# Demo.net
KiCad netlist of a schematic drawn in Altium Designer
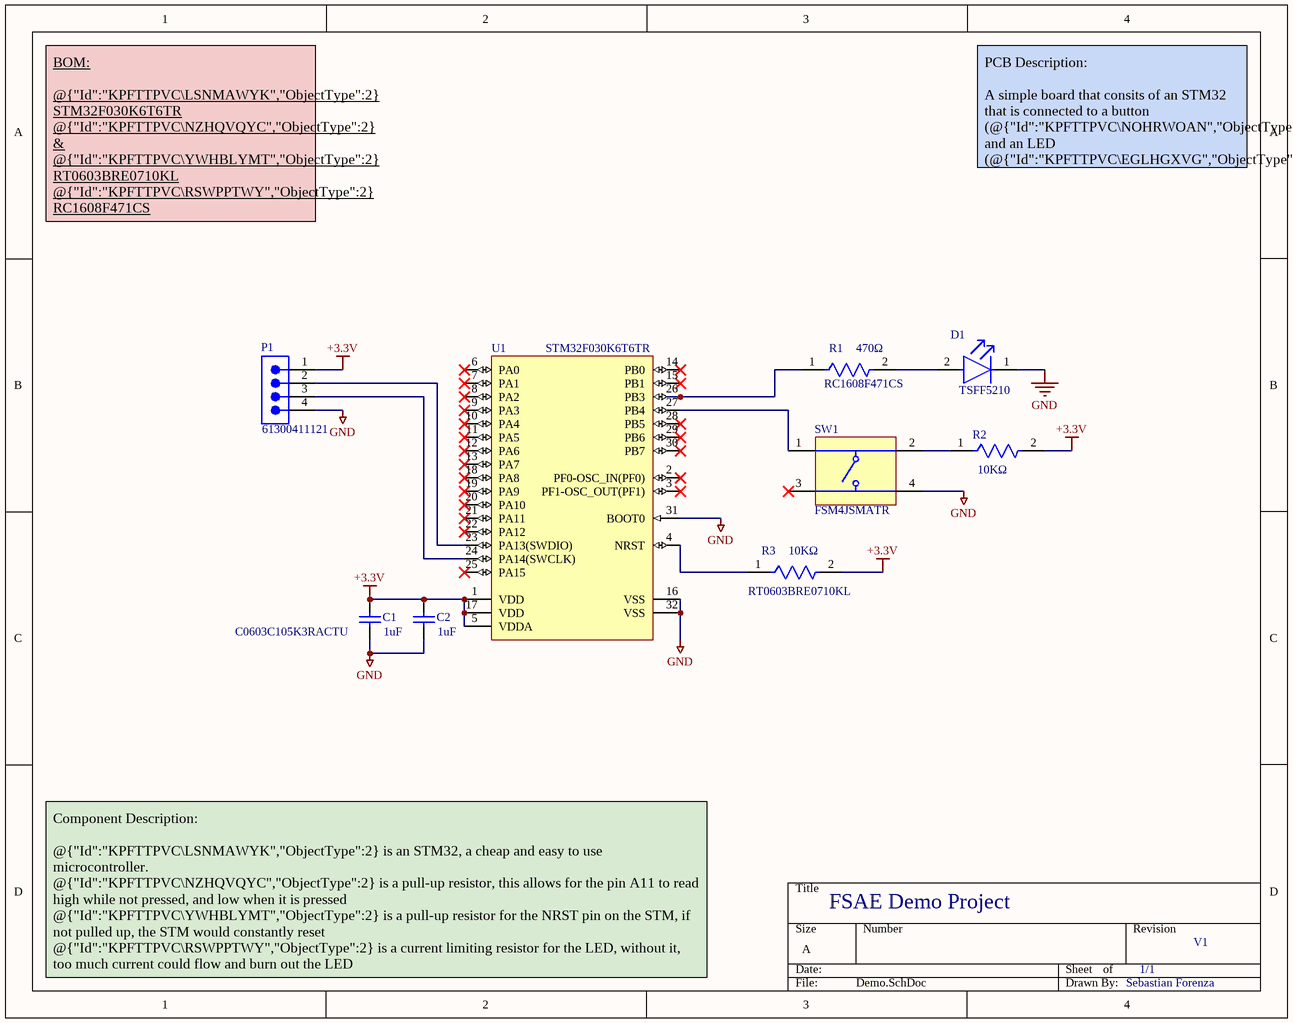
[diagram p0: Demo.SchDoc]

(export (version "E")
  (design (tool "Eeschema 10.0.6"))
  (components
    (comp (ref "C1")
      (value "C0603C105K3RACTU")
      (footprint "CAPC1608X87X35ML15T15")
      (fields (field (name "MANUFACTURER") "Kemet") (field (name "CAPACITANCE") "1uF"))
      (libsource (lib "Altium Content Vault") (part "CAP"))
    )
    (comp (ref "C2")
      (value "C0603C105K3RACTU")
      (footprint "CAPC1608X87X35ML15T15")
      (fields (field (name "MANUFACTURER") "Kemet") (field (name "CAPACITANCE") "1uF"))
      (libsource (lib "Altium Content Vault") (part "CAP"))
    )
    (comp (ref "D1")
      (value "TSFF5210")
      (footprint "FP-6_544-5258_09-4-MFG")
      (description "TSFF5210 TSFF5210 IR LED, 870nm, T-1 3/4 (5mm) Through Hole package")
      (libsource (lib "Altium Content Vault") (part "8706943c75ba83719d021d2fdc84c58"))
    )
    (comp (ref "P1")
      (value "61300411121")
      (footprint "61300411121")
      (libsource (lib "Altium Content Vault") (part "Header_Male_1R_04P"))
    )
    (comp (ref "R1")
      (value "RC1608F471CS")
      (footprint "FP-RC1608-IPC_A")
      (description "Res Thick Film 0603 470Ω 1% 0.1W ±100ppm/°C Molded SMD T/R")
      (fields (field (name "TOLERANCE") "1%") (field (name "RESISTANCE") "470Ω"))
      (libsource (lib "Altium Content Vault") (part "1029c3af85768c4190bb7ad29bc67b5"))
    )
    (comp (ref "R2")
      (value "RT0603BRE0710KL")
      (footprint "FP-RT0603-IPC_A")
      (description "RES SMD 10K OHM 0.1% 1/10W 0603")
      (fields
        (field (name "TOLERANCE") "0.001")
        (field (name "OCTOPART") "https://octopart.com/rt0603bre0710kl-yageo-1273959")
        (field (name "RESISTANCE") "10KΩ")
      )
      (libsource (lib "Altium Content Vault") (part "1029c3af85768c4190bb7ad29bc67b5"))
    )
    (comp (ref "R3")
      (value "RT0603BRE0710KL")
      (footprint "FP-RT0603-IPC_A")
      (description "RES SMD 10K OHM 0.1% 1/10W 0603")
      (fields
        (field (name "TOLERANCE") "0.001")
        (field (name "OCTOPART") "https://octopart.com/rt0603bre0710kl-yageo-1273959")
        (field (name "RESISTANCE") "10KΩ")
      )
      (libsource (lib "Altium Content Vault") (part "1029c3af85768c4190bb7ad29bc67b5"))
    )
    (comp (ref "SW1")
      (value "FSM4JSMATR")
      (footprint "TECO-FSM4JSMATR_V")
      (description "Micro Miniature Push Button Switch FSM JSM, 50 mA, -35 to 85 degC, 4-Pin SMD, RoHS, Tape and Reel")
      (fields (field (name "MANUFACTURER") "TE Connectivity"))
      (libsource (lib "Altium Content Vault") (part "SW-SPST-4_A"))
    )
    (comp (ref "U1")
      (value "STM32F030K6T6TR")
      (footprint "STM-LQFP32_M")
      (fields (field (name "MANUFACTURER") "STMicroelectronics"))
      (libsource (lib "Altium Content Vault") (part "MC-ARM-STM32F030-LQFP32"))
    )
  )
  (nets
    (net (code "1") (name "+3.3V") (class "Default")
      (node (ref "C1") (pin "2") (pinfunction "2_2") (pintype "passive"))
      (node (ref "C2") (pin "2") (pinfunction "2_2") (pintype "passive"))
      (node (ref "P1") (pin "1") (pinfunction "1_1") (pintype "passive"))
      (node (ref "R2") (pin "2") (pinfunction "2_2") (pintype "passive"))
      (node (ref "R3") (pin "2") (pinfunction "2_2") (pintype "passive"))
      (node (ref "U1") (pin "1") (pinfunction "VDD_1") (pintype "power_in"))
      (node (ref "U1") (pin "17") (pinfunction "VDD_17") (pintype "power_in"))
      (node (ref "U1") (pin "5") (pinfunction "VDDA_5") (pintype "power_in"))
    )
    (net (code "2") (name "GND") (class "Default")
      (node (ref "C1") (pin "1") (pinfunction "1_1") (pintype "passive"))
      (node (ref "C2") (pin "1") (pinfunction "1_1") (pintype "passive"))
      (node (ref "D1") (pin "1") (pinfunction "C_1") (pintype "passive"))
      (node (ref "P1") (pin "4") (pinfunction "4_4") (pintype "passive"))
      (node (ref "SW1") (pin "4") (pinfunction "4_4") (pintype "passive"))
      (node (ref "U1") (pin "16") (pinfunction "VSS_16") (pintype "power_in"))
      (node (ref "U1") (pin "31") (pinfunction "BOOT0_31") (pintype "input"))
      (node (ref "U1") (pin "32") (pinfunction "VSS_32") (pintype "power_in"))
    )
    (net (code "3") (name "Net-(D1-A)") (class "Default")
      (node (ref "D1") (pin "2") (pinfunction "A_2") (pintype "passive"))
      (node (ref "R1") (pin "2") (pinfunction "2_2") (pintype "passive"))
    )
    (net (code "4") (name "Net-(R2-Pad1)") (class "Default")
      (node (ref "R2") (pin "1") (pinfunction "1_1") (pintype "passive"))
      (node (ref "SW1") (pin "2") (pinfunction "2_2") (pintype "passive"))
    )
    (net (code "5") (name "Net-(U1-NRST)") (class "Default")
      (node (ref "R3") (pin "1") (pinfunction "1_1") (pintype "passive"))
      (node (ref "U1") (pin "4") (pinfunction "NRST_4") (pintype "bidirectional"))
    )
    (net (code "6") (name "Net-(U1-PA13(SWDIO))") (class "Default")
      (node (ref "P1") (pin "2") (pinfunction "2_2") (pintype "passive"))
      (node (ref "U1") (pin "23") (pinfunction "PA13(SWDIO)_23") (pintype "bidirectional"))
    )
    (net (code "7") (name "Net-(U1-PA14(SWCLK))") (class "Default")
      (node (ref "P1") (pin "3") (pinfunction "3_3") (pintype "passive"))
      (node (ref "U1") (pin "24") (pinfunction "PA14(SWCLK)_24") (pintype "bidirectional"))
    )
    (net (code "8") (name "Net-(U1-PB3)") (class "Default")
      (node (ref "R1") (pin "1") (pinfunction "1_1") (pintype "passive"))
      (node (ref "U1") (pin "26") (pinfunction "PB3_26") (pintype "bidirectional"))
    )
    (net (code "9") (name "Net-(U1-PB4)") (class "Default")
      (node (ref "SW1") (pin "1") (pinfunction "1_1") (pintype "passive"))
      (node (ref "U1") (pin "27") (pinfunction "PB4_27") (pintype "bidirectional"))
    )
    (net (code "10") (name "unconnected-(SW1-Pad3)") (class "Default")
      (node (ref "SW1") (pin "3") (pinfunction "3_3") (pintype "passive+no_connect"))
    )
    (net (code "11") (name "unconnected-(U1-PA0-Pad6)") (class "Default")
      (node (ref "U1") (pin "6") (pinfunction "PA0_6") (pintype "bidirectional+no_connect"))
    )
    (net (code "12") (name "unconnected-(U1-PA1-Pad7)") (class "Default")
      (node (ref "U1") (pin "7") (pinfunction "PA1_7") (pintype "bidirectional+no_connect"))
    )
    (net (code "13") (name "unconnected-(U1-PA2-Pad8)") (class "Default")
      (node (ref "U1") (pin "8") (pinfunction "PA2_8") (pintype "bidirectional+no_connect"))
    )
    (net (code "14") (name "unconnected-(U1-PA3-Pad9)") (class "Default")
      (node (ref "U1") (pin "9") (pinfunction "PA3_9") (pintype "bidirectional+no_connect"))
    )
    (net (code "15") (name "unconnected-(U1-PA4-Pad10)") (class "Default")
      (node (ref "U1") (pin "10") (pinfunction "PA4_10") (pintype "bidirectional+no_connect"))
    )
    (net (code "16") (name "unconnected-(U1-PA5-Pad11)") (class "Default")
      (node (ref "U1") (pin "11") (pinfunction "PA5_11") (pintype "bidirectional+no_connect"))
    )
    (net (code "17") (name "unconnected-(U1-PA6-Pad12)") (class "Default")
      (node (ref "U1") (pin "12") (pinfunction "PA6_12") (pintype "bidirectional+no_connect"))
    )
    (net (code "18") (name "unconnected-(U1-PA7-Pad13)") (class "Default")
      (node (ref "U1") (pin "13") (pinfunction "PA7_13") (pintype "bidirectional+no_connect"))
    )
    (net (code "19") (name "unconnected-(U1-PA8-Pad18)") (class "Default")
      (node (ref "U1") (pin "18") (pinfunction "PA8_18") (pintype "bidirectional+no_connect"))
    )
    (net (code "20") (name "unconnected-(U1-PA9-Pad19)") (class "Default")
      (node (ref "U1") (pin "19") (pinfunction "PA9_19") (pintype "bidirectional+no_connect"))
    )
    (net (code "21") (name "unconnected-(U1-PA10-Pad20)") (class "Default")
      (node (ref "U1") (pin "20") (pinfunction "PA10_20") (pintype "bidirectional+no_connect"))
    )
    (net (code "22") (name "unconnected-(U1-PA11-Pad21)") (class "Default")
      (node (ref "U1") (pin "21") (pinfunction "PA11_21") (pintype "bidirectional+no_connect"))
    )
    (net (code "23") (name "unconnected-(U1-PA12-Pad22)") (class "Default")
      (node (ref "U1") (pin "22") (pinfunction "PA12_22") (pintype "bidirectional+no_connect"))
    )
    (net (code "24") (name "unconnected-(U1-PA15-Pad25)") (class "Default")
      (node (ref "U1") (pin "25") (pinfunction "PA15_25") (pintype "bidirectional+no_connect"))
    )
    (net (code "25") (name "unconnected-(U1-PB0-Pad14)") (class "Default")
      (node (ref "U1") (pin "14") (pinfunction "PB0_14") (pintype "bidirectional+no_connect"))
    )
    (net (code "26") (name "unconnected-(U1-PB1-Pad15)") (class "Default")
      (node (ref "U1") (pin "15") (pinfunction "PB1_15") (pintype "bidirectional+no_connect"))
    )
    (net (code "27") (name "unconnected-(U1-PB5-Pad28)") (class "Default")
      (node (ref "U1") (pin "28") (pinfunction "PB5_28") (pintype "bidirectional+no_connect"))
    )
    (net (code "28") (name "unconnected-(U1-PB6-Pad29)") (class "Default")
      (node (ref "U1") (pin "29") (pinfunction "PB6_29") (pintype "bidirectional+no_connect"))
    )
    (net (code "29") (name "unconnected-(U1-PB7-Pad30)") (class "Default")
      (node (ref "U1") (pin "30") (pinfunction "PB7_30") (pintype "bidirectional+no_connect"))
    )
    (net (code "30") (name "unconnected-(U1-PF0-OSC_IN(PF0)-Pad2)") (class "Default")
      (node (ref "U1") (pin "2") (pinfunction "PF0-OSC_IN(PF0)_2") (pintype "bidirectional+no_connect"))
    )
    (net (code "31") (name "unconnected-(U1-PF1-OSC_OUT(PF1)-Pad3)") (class "Default")
      (node (ref "U1") (pin "3") (pinfunction "PF1-OSC_OUT(PF1)_3") (pintype "bidirectional+no_connect"))
    )
  )
)
